# carrier.net
KiCad netlist of a schematic drawn in EAGLE
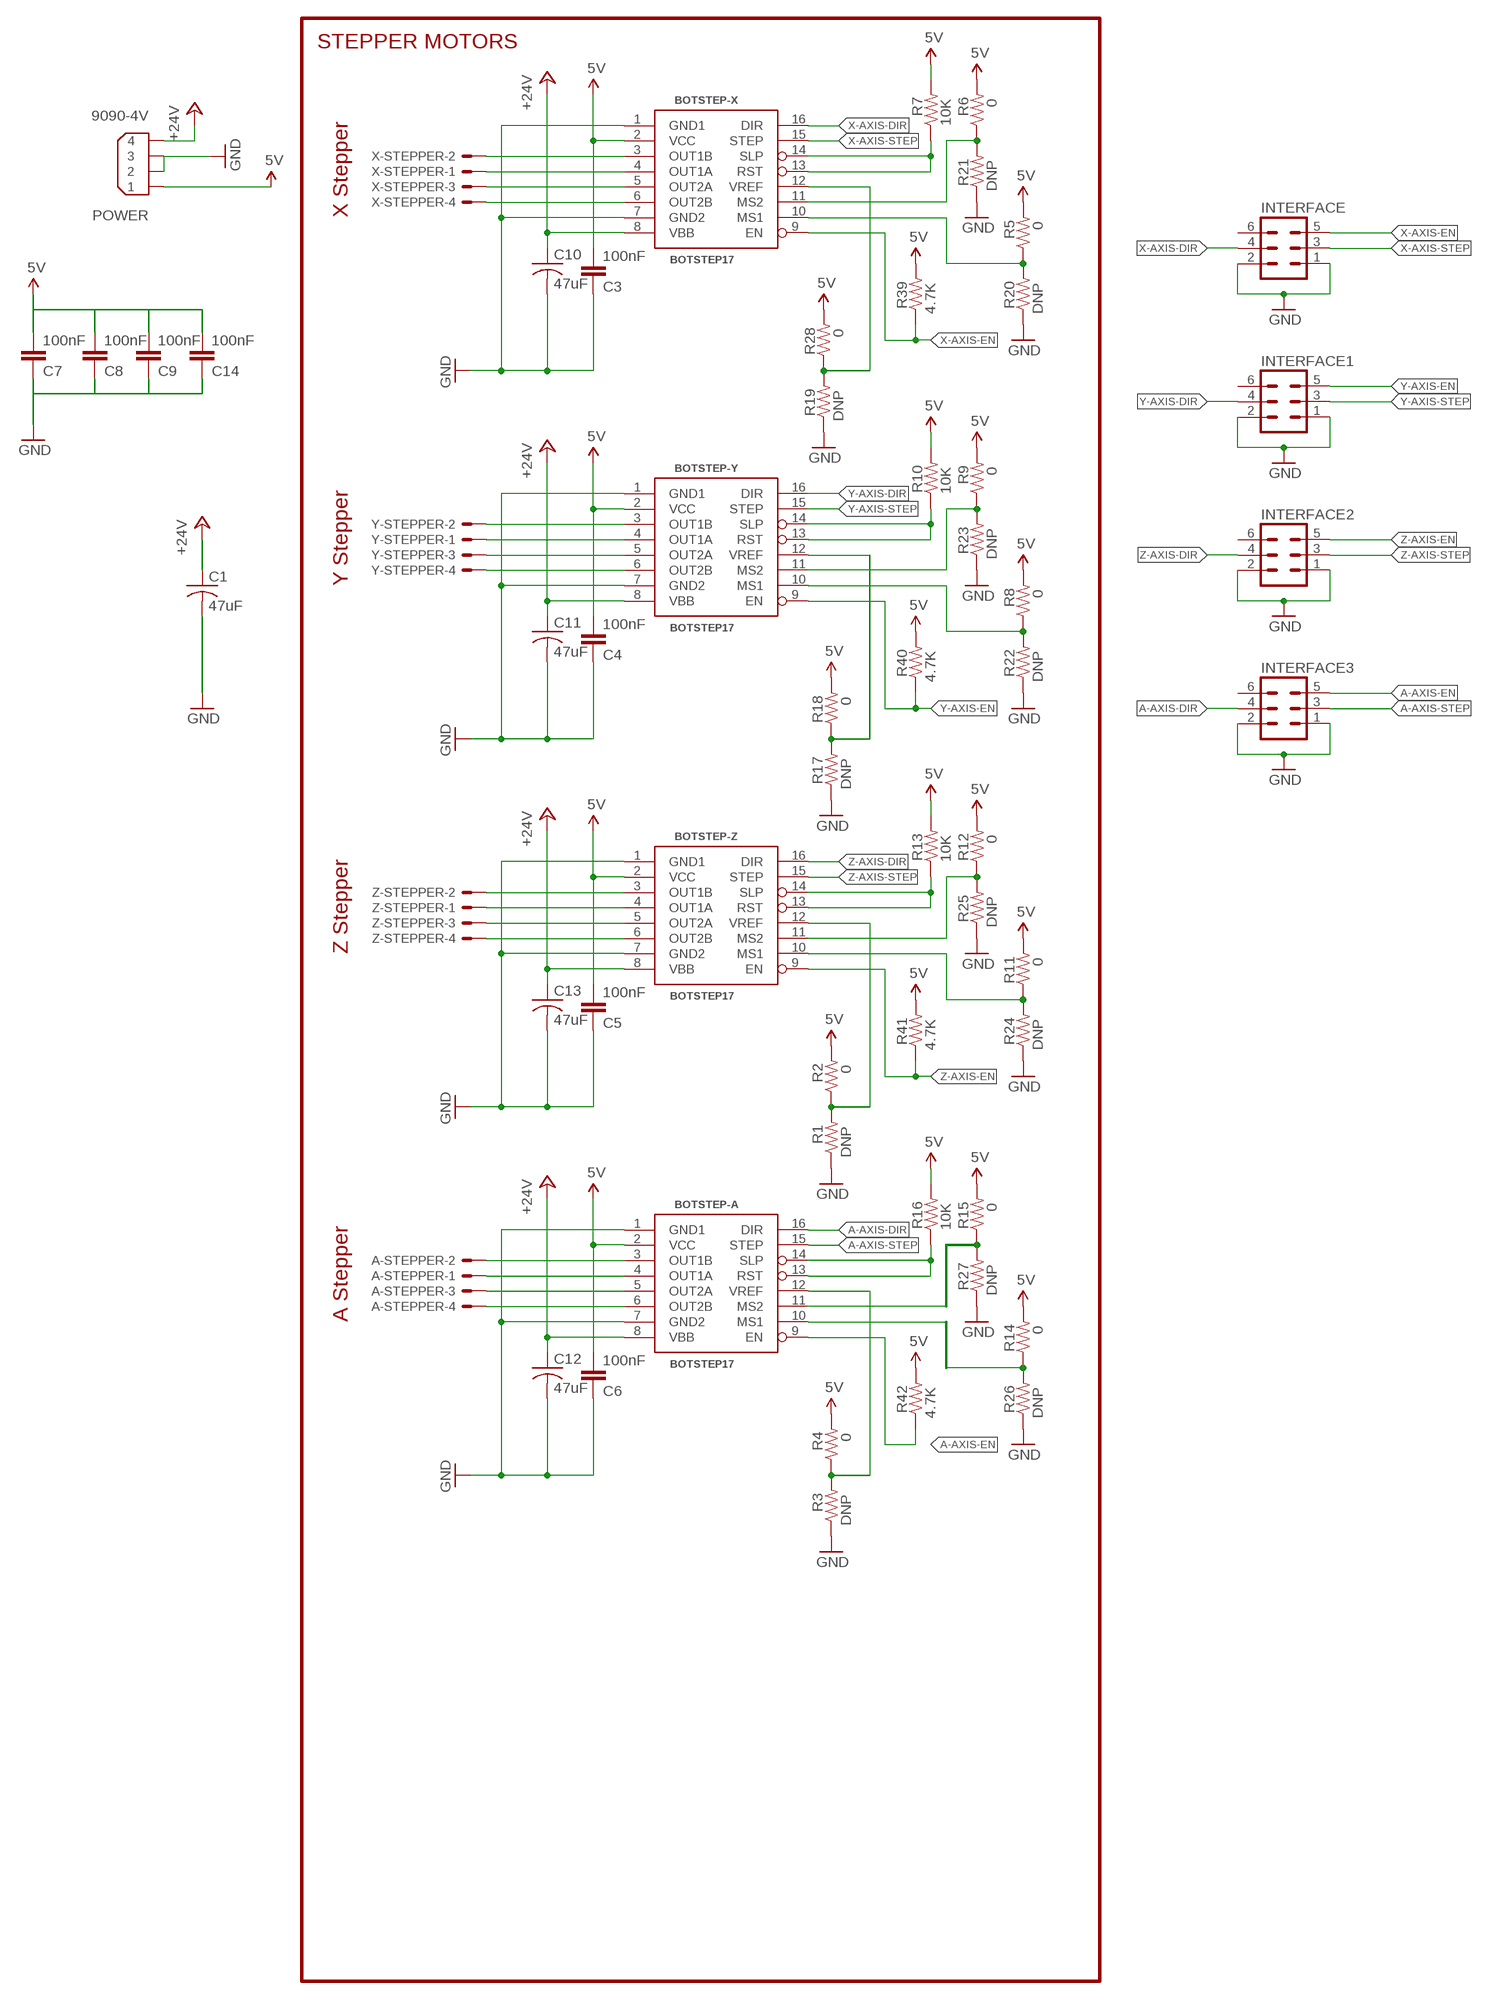
[diagram p0: schematic, sheet 1]

(export (version "E")
  (design (tool "Eeschema 10.0.6"))
  (components
    (comp (ref "A-STEPPER")
      (value "KK-156-4")
      (footprint "eagle-import:KK-156-4")
      (libsource (lib "eagle-import") (part "KK-156-4"))
    )
    (comp (ref "BOTSTEP-A")
      (value "BOTSTEP17")
      (footprint "eagle-import:BOTSTEP17-INV")
      (libsource (lib "eagle-import") (part "BOTSTEP17CHIP-DOWN"))
    )
    (comp (ref "BOTSTEP-X")
      (value "BOTSTEP17")
      (footprint "eagle-import:BOTSTEP17-INV")
      (libsource (lib "eagle-import") (part "BOTSTEP17CHIP-DOWN"))
    )
    (comp (ref "BOTSTEP-Y")
      (value "BOTSTEP17")
      (footprint "eagle-import:BOTSTEP17-INV")
      (libsource (lib "eagle-import") (part "BOTSTEP17CHIP-DOWN"))
    )
    (comp (ref "BOTSTEP-Z")
      (value "BOTSTEP17")
      (footprint "eagle-import:BOTSTEP17-INV")
      (libsource (lib "eagle-import") (part "BOTSTEP17CHIP-DOWN"))
    )
    (comp (ref "C1")
      (value "47uF")
      (footprint "eagle-import:C050-075X075")
      (libsource (lib "eagle-import") (part "C-US050-075X075"))
    )
    (comp (ref "C3")
      (value "100nF")
      (footprint "eagle-import:CAP-PTH-5MM")
      (libsource (lib "eagle-import") (part "CAPPTH1"))
    )
    (comp (ref "C4")
      (value "100nF")
      (footprint "eagle-import:CAP-PTH-5MM")
      (libsource (lib "eagle-import") (part "CAPPTH1"))
    )
    (comp (ref "C5")
      (value "100nF")
      (footprint "eagle-import:CAP-PTH-5MM")
      (libsource (lib "eagle-import") (part "CAPPTH1"))
    )
    (comp (ref "C6")
      (value "100nF")
      (footprint "eagle-import:CAP-PTH-5MM")
      (libsource (lib "eagle-import") (part "CAPPTH1"))
    )
    (comp (ref "C7")
      (value "100nF")
      (footprint "eagle-import:CAP-PTH-5MM")
      (libsource (lib "eagle-import") (part "CAPPTH1"))
    )
    (comp (ref "C8")
      (value "100nF")
      (footprint "eagle-import:CAP-PTH-5MM")
      (libsource (lib "eagle-import") (part "CAPPTH1"))
    )
    (comp (ref "C9")
      (value "100nF")
      (footprint "eagle-import:CAP-PTH-5MM")
      (libsource (lib "eagle-import") (part "CAPPTH1"))
    )
    (comp (ref "C10")
      (value "47uF")
      (footprint "eagle-import:C050-075X075")
      (libsource (lib "eagle-import") (part "C-US050-075X075"))
    )
    (comp (ref "C11")
      (value "47uF")
      (footprint "eagle-import:C050-075X075")
      (libsource (lib "eagle-import") (part "C-US050-075X075"))
    )
    (comp (ref "C12")
      (value "47uF")
      (footprint "eagle-import:C050-075X075")
      (libsource (lib "eagle-import") (part "C-US050-075X075"))
    )
    (comp (ref "C13")
      (value "47uF")
      (footprint "eagle-import:C050-075X075")
      (libsource (lib "eagle-import") (part "C-US050-075X075"))
    )
    (comp (ref "C14")
      (value "100nF")
      (footprint "eagle-import:CAP-PTH-5MM")
      (libsource (lib "eagle-import") (part "CAPPTH1"))
    )
    (comp (ref "INTERFACE")
      (value "ML6")
      (footprint "eagle-import:ML6")
      (libsource (lib "eagle-import") (part "ML6"))
    )
    (comp (ref "INTERFACE1")
      (value "ML6")
      (footprint "eagle-import:ML6")
      (libsource (lib "eagle-import") (part "ML6"))
    )
    (comp (ref "INTERFACE2")
      (value "ML6")
      (footprint "eagle-import:ML6")
      (libsource (lib "eagle-import") (part "ML6"))
    )
    (comp (ref "INTERFACE3")
      (value "ML6")
      (footprint "eagle-import:ML6")
      (libsource (lib "eagle-import") (part "ML6"))
    )
    (comp (ref "POWER")
      (value "9090-4V")
      (footprint "eagle-import:9090-4V")
      (libsource (lib "eagle-import") (part "9090-4V"))
    )
    (comp (ref "R1")
      (value "DNP")
      (footprint "eagle-import:AXIAL-0.3")
      (libsource (lib "eagle-import") (part "RESISTORPTH1"))
    )
    (comp (ref "R2")
      (value "0")
      (footprint "eagle-import:AXIAL-0.3")
      (libsource (lib "eagle-import") (part "RESISTORPTH1"))
    )
    (comp (ref "R3")
      (value "DNP")
      (footprint "eagle-import:AXIAL-0.3")
      (libsource (lib "eagle-import") (part "RESISTORPTH1"))
    )
    (comp (ref "R4")
      (value "0")
      (footprint "eagle-import:AXIAL-0.3")
      (libsource (lib "eagle-import") (part "RESISTORPTH1"))
    )
    (comp (ref "R5")
      (value "0")
      (footprint "eagle-import:AXIAL-0.3")
      (libsource (lib "eagle-import") (part "RESISTORPTH1"))
    )
    (comp (ref "R6")
      (value "0")
      (footprint "eagle-import:AXIAL-0.3")
      (libsource (lib "eagle-import") (part "RESISTORPTH1"))
    )
    (comp (ref "R7")
      (value "10K")
      (footprint "eagle-import:AXIAL-0.3")
      (libsource (lib "eagle-import") (part "RESISTORPTH1"))
    )
    (comp (ref "R8")
      (value "0")
      (footprint "eagle-import:AXIAL-0.3")
      (libsource (lib "eagle-import") (part "RESISTORPTH1"))
    )
    (comp (ref "R9")
      (value "0")
      (footprint "eagle-import:AXIAL-0.3")
      (libsource (lib "eagle-import") (part "RESISTORPTH1"))
    )
    (comp (ref "R10")
      (value "10K")
      (footprint "eagle-import:AXIAL-0.3")
      (libsource (lib "eagle-import") (part "RESISTORPTH1"))
    )
    (comp (ref "R11")
      (value "0")
      (footprint "eagle-import:AXIAL-0.3")
      (libsource (lib "eagle-import") (part "RESISTORPTH1"))
    )
    (comp (ref "R12")
      (value "0")
      (footprint "eagle-import:AXIAL-0.3")
      (libsource (lib "eagle-import") (part "RESISTORPTH1"))
    )
    (comp (ref "R13")
      (value "10K")
      (footprint "eagle-import:AXIAL-0.3")
      (libsource (lib "eagle-import") (part "RESISTORPTH1"))
    )
    (comp (ref "R14")
      (value "0")
      (footprint "eagle-import:AXIAL-0.3")
      (libsource (lib "eagle-import") (part "RESISTORPTH1"))
    )
    (comp (ref "R15")
      (value "0")
      (footprint "eagle-import:AXIAL-0.3")
      (libsource (lib "eagle-import") (part "RESISTORPTH1"))
    )
    (comp (ref "R16")
      (value "10K")
      (footprint "eagle-import:AXIAL-0.3")
      (libsource (lib "eagle-import") (part "RESISTORPTH1"))
    )
    (comp (ref "R17")
      (value "DNP")
      (footprint "eagle-import:AXIAL-0.3")
      (libsource (lib "eagle-import") (part "RESISTORPTH1"))
    )
    (comp (ref "R18")
      (value "0")
      (footprint "eagle-import:AXIAL-0.3")
      (libsource (lib "eagle-import") (part "RESISTORPTH1"))
    )
    (comp (ref "R19")
      (value "DNP")
      (footprint "eagle-import:AXIAL-0.3")
      (libsource (lib "eagle-import") (part "RESISTORPTH1"))
    )
    (comp (ref "R20")
      (value "DNP")
      (footprint "eagle-import:AXIAL-0.3")
      (libsource (lib "eagle-import") (part "RESISTORPTH1"))
    )
    (comp (ref "R21")
      (value "DNP")
      (footprint "eagle-import:AXIAL-0.3")
      (libsource (lib "eagle-import") (part "RESISTORPTH1"))
    )
    (comp (ref "R22")
      (value "DNP")
      (footprint "eagle-import:AXIAL-0.3")
      (libsource (lib "eagle-import") (part "RESISTORPTH1"))
    )
    (comp (ref "R23")
      (value "DNP")
      (footprint "eagle-import:AXIAL-0.3")
      (libsource (lib "eagle-import") (part "RESISTORPTH1"))
    )
    (comp (ref "R24")
      (value "DNP")
      (footprint "eagle-import:AXIAL-0.3")
      (libsource (lib "eagle-import") (part "RESISTORPTH1"))
    )
    (comp (ref "R25")
      (value "DNP")
      (footprint "eagle-import:AXIAL-0.3")
      (libsource (lib "eagle-import") (part "RESISTORPTH1"))
    )
    (comp (ref "R26")
      (value "DNP")
      (footprint "eagle-import:AXIAL-0.3")
      (libsource (lib "eagle-import") (part "RESISTORPTH1"))
    )
    (comp (ref "R27")
      (value "DNP")
      (footprint "eagle-import:AXIAL-0.3")
      (libsource (lib "eagle-import") (part "RESISTORPTH1"))
    )
    (comp (ref "R28")
      (value "0")
      (footprint "eagle-import:AXIAL-0.3")
      (libsource (lib "eagle-import") (part "RESISTORPTH1"))
    )
    (comp (ref "R39")
      (value "4.7K")
      (footprint "eagle-import:AXIAL-0.3")
      (libsource (lib "eagle-import") (part "RESISTORPTH1"))
    )
    (comp (ref "R40")
      (value "4.7K")
      (footprint "eagle-import:AXIAL-0.3")
      (libsource (lib "eagle-import") (part "RESISTORPTH1"))
    )
    (comp (ref "R41")
      (value "4.7K")
      (footprint "eagle-import:AXIAL-0.3")
      (libsource (lib "eagle-import") (part "RESISTORPTH1"))
    )
    (comp (ref "R42")
      (value "4.7K")
      (footprint "eagle-import:AXIAL-0.3")
      (libsource (lib "eagle-import") (part "RESISTORPTH1"))
    )
    (comp (ref "X-STEPPER")
      (value "KK-156-4")
      (footprint "eagle-import:KK-156-4")
      (libsource (lib "eagle-import") (part "KK-156-4"))
    )
    (comp (ref "Y-STEPPER")
      (value "KK-156-4")
      (footprint "eagle-import:KK-156-4")
      (libsource (lib "eagle-import") (part "KK-156-4"))
    )
    (comp (ref "Z-STEPPER")
      (value "KK-156-4")
      (footprint "eagle-import:KK-156-4")
      (libsource (lib "eagle-import") (part "KK-156-4"))
    )
  )
  (nets
    (net (code "1") (name "+24V") (class "Default")
      (node (ref "BOTSTEP-A") (pin "8") (pinfunction "VBB_8") (pintype "bidirectional"))
      (node (ref "BOTSTEP-X") (pin "8") (pinfunction "VBB_8") (pintype "bidirectional"))
      (node (ref "BOTSTEP-Y") (pin "8") (pinfunction "VBB_8") (pintype "bidirectional"))
      (node (ref "BOTSTEP-Z") (pin "8") (pinfunction "VBB_8") (pintype "bidirectional"))
      (node (ref "C1") (pin "1") (pinfunction "1_1") (pintype "passive"))
      (node (ref "C10") (pin "1") (pinfunction "1_1") (pintype "passive"))
      (node (ref "C11") (pin "1") (pinfunction "1_1") (pintype "passive"))
      (node (ref "C12") (pin "1") (pinfunction "1_1") (pintype "passive"))
      (node (ref "C13") (pin "1") (pinfunction "1_1") (pintype "passive"))
      (node (ref "POWER") (pin "4") (pinfunction "4_4") (pintype "passive"))
    )
    (net (code "2") (name "5V") (class "Default")
      (node (ref "BOTSTEP-A") (pin "2") (pinfunction "VCC_2") (pintype "bidirectional"))
      (node (ref "BOTSTEP-X") (pin "2") (pinfunction "VCC_2") (pintype "bidirectional"))
      (node (ref "BOTSTEP-Y") (pin "2") (pinfunction "VCC_2") (pintype "bidirectional"))
      (node (ref "BOTSTEP-Z") (pin "2") (pinfunction "VCC_2") (pintype "bidirectional"))
      (node (ref "C14") (pin "2") (pinfunction "2_2") (pintype "passive"))
      (node (ref "C3") (pin "2") (pinfunction "2_2") (pintype "passive"))
      (node (ref "C4") (pin "2") (pinfunction "2_2") (pintype "passive"))
      (node (ref "C5") (pin "2") (pinfunction "2_2") (pintype "passive"))
      (node (ref "C6") (pin "2") (pinfunction "2_2") (pintype "passive"))
      (node (ref "C7") (pin "2") (pinfunction "2_2") (pintype "passive"))
      (node (ref "C8") (pin "2") (pinfunction "2_2") (pintype "passive"))
      (node (ref "C9") (pin "2") (pinfunction "2_2") (pintype "passive"))
      (node (ref "POWER") (pin "1") (pinfunction "1_1") (pintype "passive"))
      (node (ref "R10") (pin "P$2") (pinfunction "2_P$2") (pintype "passive"))
      (node (ref "R11") (pin "P$2") (pinfunction "2_P$2") (pintype "passive"))
      (node (ref "R12") (pin "P$2") (pinfunction "2_P$2") (pintype "passive"))
      (node (ref "R13") (pin "P$2") (pinfunction "2_P$2") (pintype "passive"))
      (node (ref "R14") (pin "P$2") (pinfunction "2_P$2") (pintype "passive"))
      (node (ref "R15") (pin "P$2") (pinfunction "2_P$2") (pintype "passive"))
      (node (ref "R16") (pin "P$2") (pinfunction "2_P$2") (pintype "passive"))
      (node (ref "R18") (pin "P$2") (pinfunction "2_P$2") (pintype "passive"))
      (node (ref "R2") (pin "P$2") (pinfunction "2_P$2") (pintype "passive"))
      (node (ref "R28") (pin "P$2") (pinfunction "2_P$2") (pintype "passive"))
      (node (ref "R39") (pin "P$2") (pinfunction "2_P$2") (pintype "passive"))
      (node (ref "R4") (pin "P$2") (pinfunction "2_P$2") (pintype "passive"))
      (node (ref "R40") (pin "P$2") (pinfunction "2_P$2") (pintype "passive"))
      (node (ref "R41") (pin "P$2") (pinfunction "2_P$2") (pintype "passive"))
      (node (ref "R42") (pin "P$2") (pinfunction "2_P$2") (pintype "passive"))
      (node (ref "R5") (pin "P$2") (pinfunction "2_P$2") (pintype "passive"))
      (node (ref "R6") (pin "P$2") (pinfunction "2_P$2") (pintype "passive"))
      (node (ref "R7") (pin "P$2") (pinfunction "2_P$2") (pintype "passive"))
      (node (ref "R8") (pin "P$2") (pinfunction "2_P$2") (pintype "passive"))
      (node (ref "R9") (pin "P$2") (pinfunction "2_P$2") (pintype "passive"))
    )
    (net (code "3") (name "A-AXIS-DIR") (class "Default")
      (node (ref "BOTSTEP-A") (pin "16") (pinfunction "DIR_16") (pintype "input"))
      (node (ref "INTERFACE3") (pin "4") (pinfunction "4_4") (pintype "passive"))
    )
    (net (code "4") (name "A-AXIS-EN") (class "Default")
      (node (ref "BOTSTEP-A") (pin "9") (pinfunction "EN_9") (pintype "input"))
      (node (ref "INTERFACE3") (pin "5") (pinfunction "5_5") (pintype "passive"))
      (node (ref "R42") (pin "P$1") (pinfunction "1_P$1") (pintype "passive"))
    )
    (net (code "5") (name "A-AXIS-STEP") (class "Default")
      (node (ref "BOTSTEP-A") (pin "15") (pinfunction "STEP_15") (pintype "input"))
      (node (ref "INTERFACE3") (pin "3") (pinfunction "3_3") (pintype "passive"))
    )
    (net (code "6") (name "GND") (class "Default")
      (node (ref "BOTSTEP-A") (pin "1") (pinfunction "GND1_1") (pintype "bidirectional"))
      (node (ref "BOTSTEP-A") (pin "7") (pinfunction "GND2_7") (pintype "bidirectional"))
      (node (ref "BOTSTEP-X") (pin "1") (pinfunction "GND1_1") (pintype "bidirectional"))
      (node (ref "BOTSTEP-X") (pin "7") (pinfunction "GND2_7") (pintype "bidirectional"))
      (node (ref "BOTSTEP-Y") (pin "1") (pinfunction "GND1_1") (pintype "bidirectional"))
      (node (ref "BOTSTEP-Y") (pin "7") (pinfunction "GND2_7") (pintype "bidirectional"))
      (node (ref "BOTSTEP-Z") (pin "1") (pinfunction "GND1_1") (pintype "bidirectional"))
      (node (ref "BOTSTEP-Z") (pin "7") (pinfunction "GND2_7") (pintype "bidirectional"))
      (node (ref "C1") (pin "2") (pinfunction "2_2") (pintype "passive"))
      (node (ref "C10") (pin "2") (pinfunction "2_2") (pintype "passive"))
      (node (ref "C11") (pin "2") (pinfunction "2_2") (pintype "passive"))
      (node (ref "C12") (pin "2") (pinfunction "2_2") (pintype "passive"))
      (node (ref "C13") (pin "2") (pinfunction "2_2") (pintype "passive"))
      (node (ref "C14") (pin "1") (pinfunction "1_1") (pintype "passive"))
      (node (ref "C3") (pin "1") (pinfunction "1_1") (pintype "passive"))
      (node (ref "C4") (pin "1") (pinfunction "1_1") (pintype "passive"))
      (node (ref "C5") (pin "1") (pinfunction "1_1") (pintype "passive"))
      (node (ref "C6") (pin "1") (pinfunction "1_1") (pintype "passive"))
      (node (ref "C7") (pin "1") (pinfunction "1_1") (pintype "passive"))
      (node (ref "C8") (pin "1") (pinfunction "1_1") (pintype "passive"))
      (node (ref "C9") (pin "1") (pinfunction "1_1") (pintype "passive"))
      (node (ref "INTERFACE") (pin "1") (pinfunction "1_1") (pintype "passive"))
      (node (ref "INTERFACE") (pin "2") (pinfunction "2_2") (pintype "passive"))
      (node (ref "INTERFACE1") (pin "1") (pinfunction "1_1") (pintype "passive"))
      (node (ref "INTERFACE1") (pin "2") (pinfunction "2_2") (pintype "passive"))
      (node (ref "INTERFACE2") (pin "1") (pinfunction "1_1") (pintype "passive"))
      (node (ref "INTERFACE2") (pin "2") (pinfunction "2_2") (pintype "passive"))
      (node (ref "INTERFACE3") (pin "1") (pinfunction "1_1") (pintype "passive"))
      (node (ref "INTERFACE3") (pin "2") (pinfunction "2_2") (pintype "passive"))
      (node (ref "POWER") (pin "2") (pinfunction "2_2") (pintype "passive"))
      (node (ref "POWER") (pin "3") (pinfunction "3_3") (pintype "passive"))
      (node (ref "R1") (pin "P$1") (pinfunction "1_P$1") (pintype "passive"))
      (node (ref "R17") (pin "P$1") (pinfunction "1_P$1") (pintype "passive"))
      (node (ref "R19") (pin "P$1") (pinfunction "1_P$1") (pintype "passive"))
      (node (ref "R20") (pin "P$1") (pinfunction "1_P$1") (pintype "passive"))
      (node (ref "R21") (pin "P$1") (pinfunction "1_P$1") (pintype "passive"))
      (node (ref "R22") (pin "P$1") (pinfunction "1_P$1") (pintype "passive"))
      (node (ref "R23") (pin "P$1") (pinfunction "1_P$1") (pintype "passive"))
      (node (ref "R24") (pin "P$1") (pinfunction "1_P$1") (pintype "passive"))
      (node (ref "R25") (pin "P$1") (pinfunction "1_P$1") (pintype "passive"))
      (node (ref "R26") (pin "P$1") (pinfunction "1_P$1") (pintype "passive"))
      (node (ref "R27") (pin "P$1") (pinfunction "1_P$1") (pintype "passive"))
      (node (ref "R3") (pin "P$1") (pinfunction "1_P$1") (pintype "passive"))
    )
    (net (code "7") (name "Net-(A-STEPPERA-S)") (class "Default")
      (node (ref "A-STEPPER") (pin "1") (pinfunction "S_1") (pintype "passive"))
      (node (ref "BOTSTEP-A") (pin "4") (pinfunction "OUT1A_4") (pintype "output"))
    )
    (net (code "8") (name "Net-(A-STEPPERB-S)") (class "Default")
      (node (ref "A-STEPPER") (pin "2") (pinfunction "S_2") (pintype "passive"))
      (node (ref "BOTSTEP-A") (pin "3") (pinfunction "OUT1B_3") (pintype "output"))
    )
    (net (code "9") (name "Net-(A-STEPPERC-S)") (class "Default")
      (node (ref "A-STEPPER") (pin "3") (pinfunction "S_3") (pintype "passive"))
      (node (ref "BOTSTEP-A") (pin "5") (pinfunction "OUT2A_5") (pintype "output"))
    )
    (net (code "10") (name "Net-(A-STEPPERD-S)") (class "Default")
      (node (ref "A-STEPPER") (pin "4") (pinfunction "S_4") (pintype "passive"))
      (node (ref "BOTSTEP-A") (pin "6") (pinfunction "OUT2B_6") (pintype "output"))
    )
    (net (code "11") (name "Net-(BOTSTEP-A-MS1)") (class "Default")
      (node (ref "BOTSTEP-A") (pin "10") (pinfunction "MS1_10") (pintype "input"))
      (node (ref "R14") (pin "P$1") (pinfunction "1_P$1") (pintype "passive"))
      (node (ref "R26") (pin "P$2") (pinfunction "2_P$2") (pintype "passive"))
    )
    (net (code "12") (name "Net-(BOTSTEP-A-MS2)") (class "Default")
      (node (ref "BOTSTEP-A") (pin "11") (pinfunction "MS2_11") (pintype "input"))
      (node (ref "R15") (pin "P$1") (pinfunction "1_P$1") (pintype "passive"))
      (node (ref "R27") (pin "P$2") (pinfunction "2_P$2") (pintype "passive"))
    )
    (net (code "13") (name "Net-(BOTSTEP-A-RST)") (class "Default")
      (node (ref "BOTSTEP-A") (pin "13") (pinfunction "RST_13") (pintype "input"))
      (node (ref "BOTSTEP-A") (pin "14") (pinfunction "SLP_14") (pintype "input"))
      (node (ref "R16") (pin "P$1") (pinfunction "1_P$1") (pintype "passive"))
    )
    (net (code "14") (name "Net-(BOTSTEP-A-VREF)") (class "Default")
      (node (ref "BOTSTEP-A") (pin "12") (pinfunction "VREF_12") (pintype "input"))
      (node (ref "R3") (pin "P$2") (pinfunction "2_P$2") (pintype "passive"))
      (node (ref "R4") (pin "P$1") (pinfunction "1_P$1") (pintype "passive"))
    )
    (net (code "15") (name "Net-(BOTSTEP-X-MS1)") (class "Default")
      (node (ref "BOTSTEP-X") (pin "10") (pinfunction "MS1_10") (pintype "input"))
      (node (ref "R20") (pin "P$2") (pinfunction "2_P$2") (pintype "passive"))
      (node (ref "R5") (pin "P$1") (pinfunction "1_P$1") (pintype "passive"))
    )
    (net (code "16") (name "Net-(BOTSTEP-X-MS2)") (class "Default")
      (node (ref "BOTSTEP-X") (pin "11") (pinfunction "MS2_11") (pintype "input"))
      (node (ref "R21") (pin "P$2") (pinfunction "2_P$2") (pintype "passive"))
      (node (ref "R6") (pin "P$1") (pinfunction "1_P$1") (pintype "passive"))
    )
    (net (code "17") (name "Net-(BOTSTEP-X-OUT1A)") (class "Default")
      (node (ref "BOTSTEP-X") (pin "4") (pinfunction "OUT1A_4") (pintype "output"))
      (node (ref "X-STEPPER") (pin "1") (pinfunction "S_1") (pintype "passive"))
    )
    (net (code "18") (name "Net-(BOTSTEP-X-OUT1B)") (class "Default")
      (node (ref "BOTSTEP-X") (pin "3") (pinfunction "OUT1B_3") (pintype "output"))
      (node (ref "X-STEPPER") (pin "2") (pinfunction "S_2") (pintype "passive"))
    )
    (net (code "19") (name "Net-(BOTSTEP-X-OUT2A)") (class "Default")
      (node (ref "BOTSTEP-X") (pin "5") (pinfunction "OUT2A_5") (pintype "output"))
      (node (ref "X-STEPPER") (pin "3") (pinfunction "S_3") (pintype "passive"))
    )
    (net (code "20") (name "Net-(BOTSTEP-X-OUT2B)") (class "Default")
      (node (ref "BOTSTEP-X") (pin "6") (pinfunction "OUT2B_6") (pintype "output"))
      (node (ref "X-STEPPER") (pin "4") (pinfunction "S_4") (pintype "passive"))
    )
    (net (code "21") (name "Net-(BOTSTEP-X-RST)") (class "Default")
      (node (ref "BOTSTEP-X") (pin "13") (pinfunction "RST_13") (pintype "input"))
      (node (ref "BOTSTEP-X") (pin "14") (pinfunction "SLP_14") (pintype "input"))
      (node (ref "R7") (pin "P$1") (pinfunction "1_P$1") (pintype "passive"))
    )
    (net (code "22") (name "Net-(BOTSTEP-X-VREF)") (class "Default")
      (node (ref "BOTSTEP-X") (pin "12") (pinfunction "VREF_12") (pintype "input"))
      (node (ref "R19") (pin "P$2") (pinfunction "2_P$2") (pintype "passive"))
      (node (ref "R28") (pin "P$1") (pinfunction "1_P$1") (pintype "passive"))
    )
    (net (code "23") (name "Net-(BOTSTEP-Y-MS1)") (class "Default")
      (node (ref "BOTSTEP-Y") (pin "10") (pinfunction "MS1_10") (pintype "input"))
      (node (ref "R22") (pin "P$2") (pinfunction "2_P$2") (pintype "passive"))
      (node (ref "R8") (pin "P$1") (pinfunction "1_P$1") (pintype "passive"))
    )
    (net (code "24") (name "Net-(BOTSTEP-Y-MS2)") (class "Default")
      (node (ref "BOTSTEP-Y") (pin "11") (pinfunction "MS2_11") (pintype "input"))
      (node (ref "R23") (pin "P$2") (pinfunction "2_P$2") (pintype "passive"))
      (node (ref "R9") (pin "P$1") (pinfunction "1_P$1") (pintype "passive"))
    )
    (net (code "25") (name "Net-(BOTSTEP-Y-OUT1A)") (class "Default")
      (node (ref "BOTSTEP-Y") (pin "4") (pinfunction "OUT1A_4") (pintype "output"))
      (node (ref "Y-STEPPER") (pin "1") (pinfunction "S_1") (pintype "passive"))
    )
    (net (code "26") (name "Net-(BOTSTEP-Y-OUT1B)") (class "Default")
      (node (ref "BOTSTEP-Y") (pin "3") (pinfunction "OUT1B_3") (pintype "output"))
      (node (ref "Y-STEPPER") (pin "2") (pinfunction "S_2") (pintype "passive"))
    )
    (net (code "27") (name "Net-(BOTSTEP-Y-OUT2A)") (class "Default")
      (node (ref "BOTSTEP-Y") (pin "5") (pinfunction "OUT2A_5") (pintype "output"))
      (node (ref "Y-STEPPER") (pin "3") (pinfunction "S_3") (pintype "passive"))
    )
    (net (code "28") (name "Net-(BOTSTEP-Y-OUT2B)") (class "Default")
      (node (ref "BOTSTEP-Y") (pin "6") (pinfunction "OUT2B_6") (pintype "output"))
      (node (ref "Y-STEPPER") (pin "4") (pinfunction "S_4") (pintype "passive"))
    )
    (net (code "29") (name "Net-(BOTSTEP-Y-RST)") (class "Default")
      (node (ref "BOTSTEP-Y") (pin "13") (pinfunction "RST_13") (pintype "input"))
      (node (ref "BOTSTEP-Y") (pin "14") (pinfunction "SLP_14") (pintype "input"))
      (node (ref "R10") (pin "P$1") (pinfunction "1_P$1") (pintype "passive"))
    )
    (net (code "30") (name "Net-(BOTSTEP-Y-VREF)") (class "Default")
      (node (ref "BOTSTEP-Y") (pin "12") (pinfunction "VREF_12") (pintype "input"))
      (node (ref "R17") (pin "P$2") (pinfunction "2_P$2") (pintype "passive"))
      (node (ref "R18") (pin "P$1") (pinfunction "1_P$1") (pintype "passive"))
    )
    (net (code "31") (name "Net-(BOTSTEP-Z-MS1)") (class "Default")
      (node (ref "BOTSTEP-Z") (pin "10") (pinfunction "MS1_10") (pintype "input"))
      (node (ref "R11") (pin "P$1") (pinfunction "1_P$1") (pintype "passive"))
      (node (ref "R24") (pin "P$2") (pinfunction "2_P$2") (pintype "passive"))
    )
    (net (code "32") (name "Net-(BOTSTEP-Z-MS2)") (class "Default")
      (node (ref "BOTSTEP-Z") (pin "11") (pinfunction "MS2_11") (pintype "input"))
      (node (ref "R12") (pin "P$1") (pinfunction "1_P$1") (pintype "passive"))
      (node (ref "R25") (pin "P$2") (pinfunction "2_P$2") (pintype "passive"))
    )
    (net (code "33") (name "Net-(BOTSTEP-Z-OUT1A)") (class "Default")
      (node (ref "BOTSTEP-Z") (pin "4") (pinfunction "OUT1A_4") (pintype "output"))
      (node (ref "Z-STEPPER") (pin "1") (pinfunction "S_1") (pintype "passive"))
    )
    (net (code "34") (name "Net-(BOTSTEP-Z-OUT1B)") (class "Default")
      (node (ref "BOTSTEP-Z") (pin "3") (pinfunction "OUT1B_3") (pintype "output"))
      (node (ref "Z-STEPPER") (pin "2") (pinfunction "S_2") (pintype "passive"))
    )
    (net (code "35") (name "Net-(BOTSTEP-Z-OUT2A)") (class "Default")
      (node (ref "BOTSTEP-Z") (pin "5") (pinfunction "OUT2A_5") (pintype "output"))
      (node (ref "Z-STEPPER") (pin "3") (pinfunction "S_3") (pintype "passive"))
    )
    (net (code "36") (name "Net-(BOTSTEP-Z-OUT2B)") (class "Default")
      (node (ref "BOTSTEP-Z") (pin "6") (pinfunction "OUT2B_6") (pintype "output"))
      (node (ref "Z-STEPPER") (pin "4") (pinfunction "S_4") (pintype "passive"))
    )
    (net (code "37") (name "Net-(BOTSTEP-Z-RST)") (class "Default")
      (node (ref "BOTSTEP-Z") (pin "13") (pinfunction "RST_13") (pintype "input"))
      (node (ref "BOTSTEP-Z") (pin "14") (pinfunction "SLP_14") (pintype "input"))
      (node (ref "R13") (pin "P$1") (pinfunction "1_P$1") (pintype "passive"))
    )
    (net (code "38") (name "Net-(BOTSTEP-Z-VREF)") (class "Default")
      (node (ref "BOTSTEP-Z") (pin "12") (pinfunction "VREF_12") (pintype "input"))
      (node (ref "R1") (pin "P$2") (pinfunction "2_P$2") (pintype "passive"))
      (node (ref "R2") (pin "P$1") (pinfunction "1_P$1") (pintype "passive"))
    )
    (net (code "39") (name "X-AXIS-DIR") (class "Default")
      (node (ref "BOTSTEP-X") (pin "16") (pinfunction "DIR_16") (pintype "input"))
      (node (ref "INTERFACE") (pin "4") (pinfunction "4_4") (pintype "passive"))
    )
    (net (code "40") (name "X-AXIS-EN") (class "Default")
      (node (ref "BOTSTEP-X") (pin "9") (pinfunction "EN_9") (pintype "input"))
      (node (ref "INTERFACE") (pin "5") (pinfunction "5_5") (pintype "passive"))
      (node (ref "R39") (pin "P$1") (pinfunction "1_P$1") (pintype "passive"))
    )
    (net (code "41") (name "X-AXIS-STEP") (class "Default")
      (node (ref "BOTSTEP-X") (pin "15") (pinfunction "STEP_15") (pintype "input"))
      (node (ref "INTERFACE") (pin "3") (pinfunction "3_3") (pintype "passive"))
    )
    (net (code "42") (name "Y-AXIS-DIR") (class "Default")
      (node (ref "BOTSTEP-Y") (pin "16") (pinfunction "DIR_16") (pintype "input"))
      (node (ref "INTERFACE1") (pin "4") (pinfunction "4_4") (pintype "passive"))
    )
    (net (code "43") (name "Y-AXIS-EN") (class "Default")
      (node (ref "BOTSTEP-Y") (pin "9") (pinfunction "EN_9") (pintype "input"))
      (node (ref "INTERFACE1") (pin "5") (pinfunction "5_5") (pintype "passive"))
      (node (ref "R40") (pin "P$1") (pinfunction "1_P$1") (pintype "passive"))
    )
    (net (code "44") (name "Y-AXIS-STEP") (class "Default")
      (node (ref "BOTSTEP-Y") (pin "15") (pinfunction "STEP_15") (pintype "input"))
      (node (ref "INTERFACE1") (pin "3") (pinfunction "3_3") (pintype "passive"))
    )
    (net (code "45") (name "Z-AXIS-DIR") (class "Default")
      (node (ref "BOTSTEP-Z") (pin "16") (pinfunction "DIR_16") (pintype "input"))
      (node (ref "INTERFACE2") (pin "4") (pinfunction "4_4") (pintype "passive"))
    )
    (net (code "46") (name "Z-AXIS-EN") (class "Default")
      (node (ref "BOTSTEP-Z") (pin "9") (pinfunction "EN_9") (pintype "input"))
      (node (ref "INTERFACE2") (pin "5") (pinfunction "5_5") (pintype "passive"))
      (node (ref "R41") (pin "P$1") (pinfunction "1_P$1") (pintype "passive"))
    )
    (net (code "47") (name "Z-AXIS-STEP") (class "Default")
      (node (ref "BOTSTEP-Z") (pin "15") (pinfunction "STEP_15") (pintype "input"))
      (node (ref "INTERFACE2") (pin "3") (pinfunction "3_3") (pintype "passive"))
    )
    (net (code "48") (name "unconnected-(INTERFACE-Pad6)") (class "Default")
      (node (ref "INTERFACE") (pin "6") (pinfunction "6_6") (pintype "passive"))
    )
    (net (code "49") (name "unconnected-(INTERFACE1-Pad6)") (class "Default")
      (node (ref "INTERFACE1") (pin "6") (pinfunction "6_6") (pintype "passive"))
    )
    (net (code "50") (name "unconnected-(INTERFACE2-Pad6)") (class "Default")
      (node (ref "INTERFACE2") (pin "6") (pinfunction "6_6") (pintype "passive"))
    )
    (net (code "51") (name "unconnected-(INTERFACE3-Pad6)") (class "Default")
      (node (ref "INTERFACE3") (pin "6") (pinfunction "6_6") (pintype "passive"))
    )
  )
)
